# Sheet1.net
KiCad netlist of a schematic drawn in Altium Designer
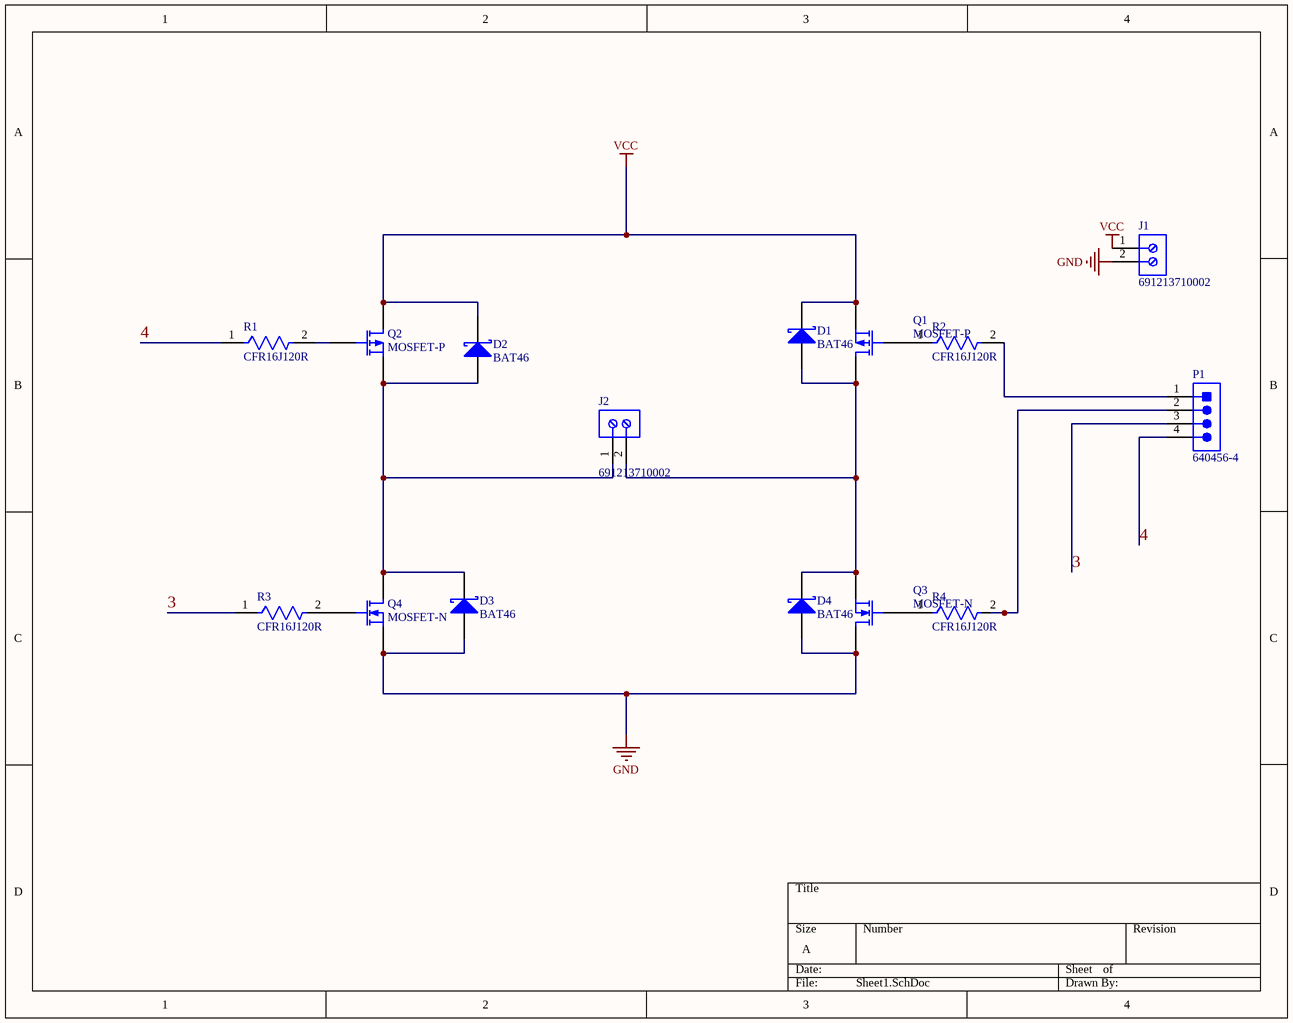
[diagram p0: Sheet1.SchDoc]

(export (version "E")
  (design (tool "Eeschema 10.0.6"))
  (components
    (comp (ref "D1")
      (value "BAT46")
      (footprint "STM-DO-35-2")
      (description "Small Signal Schottky Diode, 150 mA, 100 V, -65 to 125 degC, 2-Pin DO-35, RoHS, Tape and Reel")
      (fields (field (name "MANUFACTURER") "STMicroelectronics"))
      (libsource (lib "Altium Content Vault") (part "DSKY-AK-2"))
    )
    (comp (ref "D2")
      (value "BAT46")
      (footprint "STM-DO-35-2")
      (description "Small Signal Schottky Diode, 150 mA, 100 V, -65 to 125 degC, 2-Pin DO-35, RoHS, Tape and Reel")
      (fields (field (name "MANUFACTURER") "STMicroelectronics"))
      (libsource (lib "Altium Content Vault") (part "DSKY-AK-2"))
    )
    (comp (ref "D3")
      (value "BAT46")
      (footprint "STM-DO-35-2")
      (description "Small Signal Schottky Diode, 150 mA, 100 V, -65 to 125 degC, 2-Pin DO-35, RoHS, Tape and Reel")
      (fields (field (name "MANUFACTURER") "STMicroelectronics"))
      (libsource (lib "Altium Content Vault") (part "DSKY-AK-2"))
    )
    (comp (ref "D4")
      (value "BAT46")
      (footprint "STM-DO-35-2")
      (description "Small Signal Schottky Diode, 150 mA, 100 V, -65 to 125 degC, 2-Pin DO-35, RoHS, Tape and Reel")
      (fields (field (name "MANUFACTURER") "STMicroelectronics"))
      (libsource (lib "Altium Content Vault") (part "DSKY-AK-2"))
    )
    (comp (ref "J1")
      (value "691213710002")
      (footprint "691213710002")
      (fields (field (name "VOLTAGE") "300V"))
      (libsource (lib "Altium Content Vault") (part "TBL - 1R - 02P - Screw"))
    )
    (comp (ref "J2")
      (value "691213710002")
      (footprint "691213710002")
      (fields (field (name "VOLTAGE") "300V"))
      (libsource (lib "Altium Content Vault") (part "TBL - 1R - 02P - Screw"))
    )
    (comp (ref "P1")
      (value "640456-4")
      (footprint "TECO-640456-4")
      (description "Male Header, Pitch 2.54 mm, 1 x 4 Position, Height 10.03 mm, Tail Length 3.56 mm, RoHS, Bulk")
      (fields (field (name "MANUFACTURER") "TE Connectivity"))
      (libsource (lib "Altium Content Vault") (part "CN-1P-M-R4"))
    )
    (comp (ref "Q1")
      (value "MOSFET-P")
      (footprint "E3")
      (description "P-Channel MOSFET")
      (fields (field (name "PUBLISHER") "Altium Limited"))
      (libsource (lib "Miscellaneous Devices") (part "MOSFET-P"))
    )
    (comp (ref "Q2")
      (value "MOSFET-P")
      (footprint "E3")
      (description "P-Channel MOSFET")
      (fields (field (name "PUBLISHER") "Altium Limited"))
      (libsource (lib "Miscellaneous Devices") (part "MOSFET-P"))
    )
    (comp (ref "Q3")
      (value "MOSFET-N")
      (footprint "E3")
      (description "N-Channel MOSFET")
      (fields (field (name "PUBLISHER") "Altium Limited"))
      (libsource (lib "Miscellaneous Devices") (part "MOSFET-N"))
    )
    (comp (ref "Q4")
      (value "MOSFET-N")
      (footprint "E3")
      (description "N-Channel MOSFET")
      (fields (field (name "PUBLISHER") "Altium Limited"))
      (libsource (lib "Miscellaneous Devices") (part "MOSFET-N"))
    )
    (comp (ref "R1")
      (value "CFR16J120R")
      (footprint "FP-CFR16-MFG")
      (description "RES 120 OHM 1/4W 5% AXIAL")
      (fields (field (name "TOLERANCE") "5%"))
      (libsource (lib "Altium Content Vault") (part "1029c3af85768c4190bb7ad29bc67b5"))
    )
    (comp (ref "R2")
      (value "CFR16J120R")
      (footprint "FP-CFR16-MFG")
      (description "RES 120 OHM 1/4W 5% AXIAL")
      (fields (field (name "TOLERANCE") "5%"))
      (libsource (lib "Altium Content Vault") (part "1029c3af85768c4190bb7ad29bc67b5"))
    )
    (comp (ref "R3")
      (value "CFR16J120R")
      (footprint "FP-CFR16-MFG")
      (description "RES 120 OHM 1/4W 5% AXIAL")
      (fields (field (name "TOLERANCE") "5%"))
      (libsource (lib "Altium Content Vault") (part "1029c3af85768c4190bb7ad29bc67b5"))
    )
    (comp (ref "R4")
      (value "CFR16J120R")
      (footprint "FP-CFR16-MFG")
      (description "RES 120 OHM 1/4W 5% AXIAL")
      (fields (field (name "TOLERANCE") "5%"))
      (libsource (lib "Altium Content Vault") (part "1029c3af85768c4190bb7ad29bc67b5"))
    )
  )
  (nets
    (net (code "1") (name "/3") (class "Default")
      (node (ref "P1") (pin "3") (pinfunction "3_3") (pintype "passive"))
      (node (ref "R3") (pin "1") (pinfunction "1_1") (pintype "passive"))
    )
    (net (code "2") (name "/4") (class "Default")
      (node (ref "P1") (pin "4") (pinfunction "4_4") (pintype "passive"))
      (node (ref "R1") (pin "1") (pinfunction "1_1") (pintype "passive"))
    )
    (net (code "3") (name "GND") (class "Default")
      (node (ref "D3") (pin "1") (pinfunction "A_1") (pintype "passive"))
      (node (ref "D4") (pin "1") (pinfunction "A_1") (pintype "passive"))
      (node (ref "J1") (pin "2") (pinfunction "2_2") (pintype "passive"))
      (node (ref "Q3") (pin "1") (pinfunction "D_1") (pintype "passive"))
      (node (ref "Q4") (pin "3") (pinfunction "S_3") (pintype "passive"))
    )
    (net (code "4") (name "Net-(D1-A)") (class "Default")
      (node (ref "D1") (pin "1") (pinfunction "A_1") (pintype "passive"))
      (node (ref "D4") (pin "2") (pinfunction "K_2") (pintype "passive"))
      (node (ref "J2") (pin "2") (pinfunction "2_2") (pintype "passive"))
      (node (ref "Q1") (pin "1") (pinfunction "D_1") (pintype "passive"))
      (node (ref "Q3") (pin "3") (pinfunction "S_3") (pintype "passive"))
    )
    (net (code "5") (name "Net-(D2-A)") (class "Default")
      (node (ref "D2") (pin "1") (pinfunction "A_1") (pintype "passive"))
      (node (ref "D3") (pin "2") (pinfunction "K_2") (pintype "passive"))
      (node (ref "J2") (pin "1") (pinfunction "1_1") (pintype "passive"))
      (node (ref "Q2") (pin "3") (pinfunction "S_3") (pintype "passive"))
      (node (ref "Q4") (pin "1") (pinfunction "D_1") (pintype "passive"))
    )
    (net (code "6") (name "Net-(P1-Pad1)") (class "Default")
      (node (ref "P1") (pin "1") (pinfunction "1_1") (pintype "passive"))
      (node (ref "R2") (pin "2") (pinfunction "2_2") (pintype "passive"))
    )
    (net (code "7") (name "Net-(P1-Pad2)") (class "Default")
      (node (ref "P1") (pin "2") (pinfunction "2_2") (pintype "passive"))
      (node (ref "R4") (pin "2") (pinfunction "2_2") (pintype "passive"))
    )
    (net (code "8") (name "Net-(Q1-G)") (class "Default")
      (node (ref "Q1") (pin "2") (pinfunction "G_2") (pintype "passive"))
      (node (ref "R2") (pin "1") (pinfunction "1_1") (pintype "passive"))
    )
    (net (code "9") (name "Net-(Q2-G)") (class "Default")
      (node (ref "Q2") (pin "2") (pinfunction "G_2") (pintype "passive"))
      (node (ref "R1") (pin "2") (pinfunction "2_2") (pintype "passive"))
    )
    (net (code "10") (name "Net-(Q3-G)") (class "Default")
      (node (ref "Q3") (pin "2") (pinfunction "G_2") (pintype "passive"))
      (node (ref "R4") (pin "1") (pinfunction "1_1") (pintype "passive"))
    )
    (net (code "11") (name "Net-(Q4-G)") (class "Default")
      (node (ref "Q4") (pin "2") (pinfunction "G_2") (pintype "passive"))
      (node (ref "R3") (pin "2") (pinfunction "2_2") (pintype "passive"))
    )
    (net (code "12") (name "VCC") (class "Default")
      (node (ref "D1") (pin "2") (pinfunction "K_2") (pintype "passive"))
      (node (ref "D2") (pin "2") (pinfunction "K_2") (pintype "passive"))
      (node (ref "J1") (pin "1") (pinfunction "1_1") (pintype "passive"))
      (node (ref "Q1") (pin "3") (pinfunction "S_3") (pintype "passive"))
      (node (ref "Q2") (pin "1") (pinfunction "D_1") (pintype "passive"))
    )
  )
)
